# PCB_DYBoard_Collector_V1_Sh2.net
KiCad netlist of a schematic drawn in Altium Designer
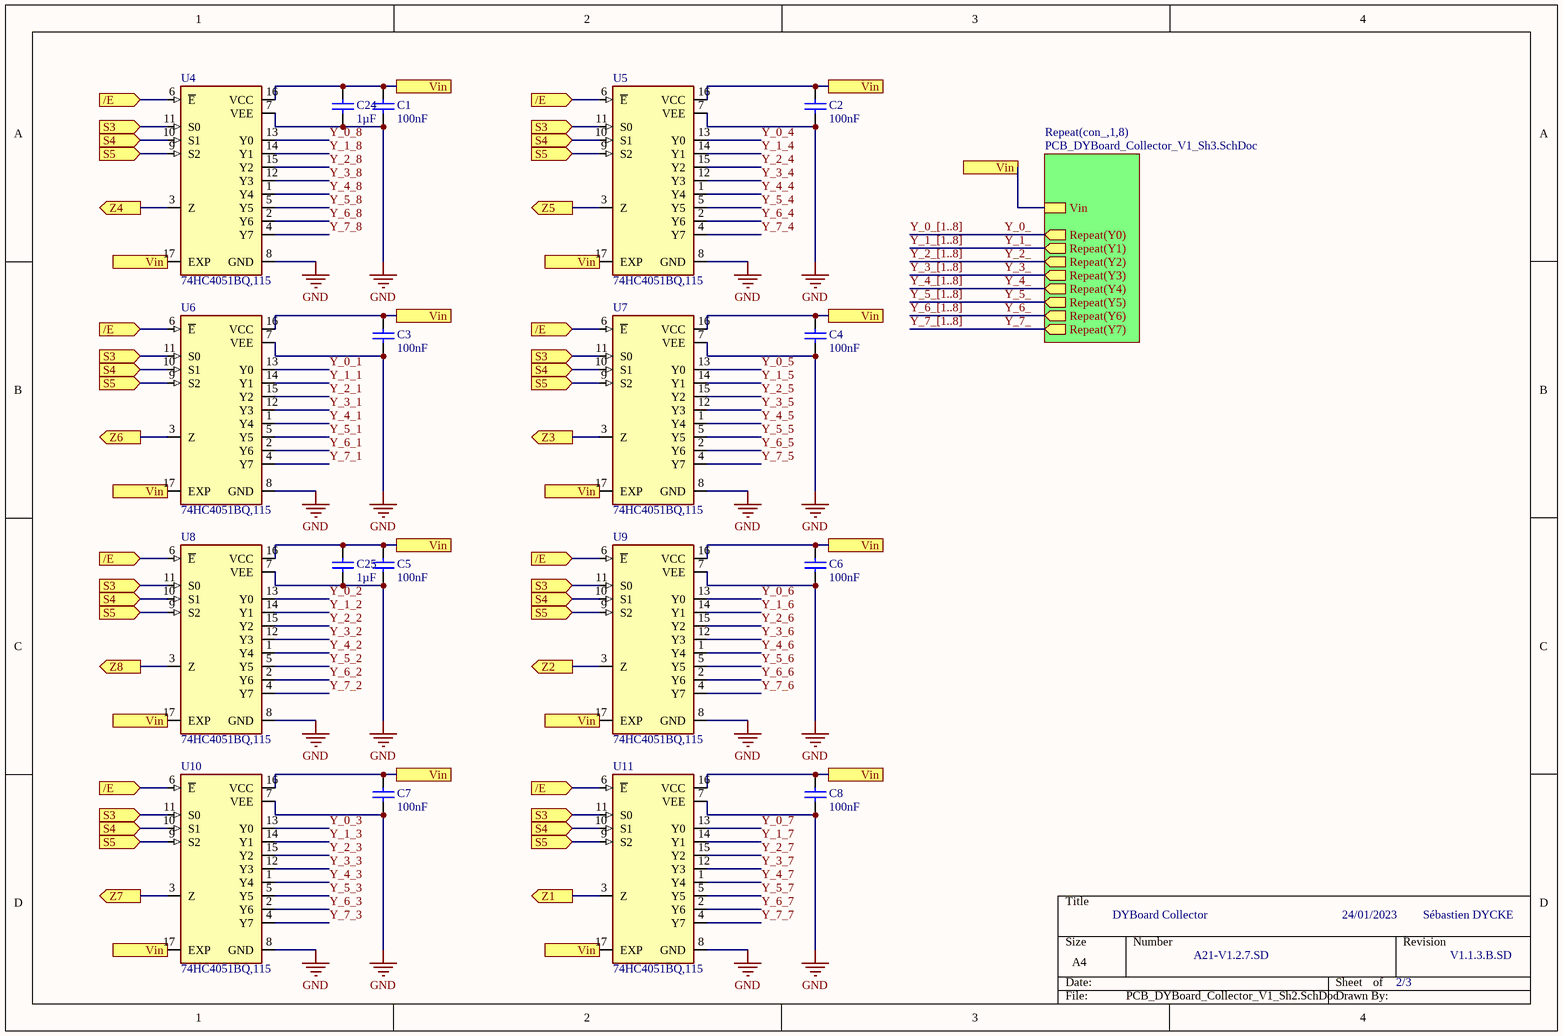
[diagram p0: PCB_DYBoard_Collector_V1_Sh2.SchDoc]

(export (version "E")
  (design (tool "Eeschema 10.0.6"))
  (components
    (comp (ref "C1")
      (value "100nF")
      (footprint "1608[0603]")
      (description "Capacitor (Semiconductor SIM Model)")
      (fields (field (name "Comment") "Cap Semi") (field (name "PUBLISHER") "Altium Limited"))
      (libsource (lib "Miscellaneous Devices") (part "Cap Semi"))
    )
    (comp (ref "C2")
      (value "100nF")
      (footprint "1608[0603]")
      (description "Capacitor (Semiconductor SIM Model)")
      (fields (field (name "Comment") "Cap Semi") (field (name "PUBLISHER") "Altium Limited"))
      (libsource (lib "Miscellaneous Devices") (part "Cap Semi"))
    )
    (comp (ref "C3")
      (value "100nF")
      (footprint "1608[0603]")
      (description "Capacitor (Semiconductor SIM Model)")
      (fields (field (name "Comment") "Cap Semi") (field (name "PUBLISHER") "Altium Limited"))
      (libsource (lib "Miscellaneous Devices") (part "Cap Semi"))
    )
    (comp (ref "C4")
      (value "100nF")
      (footprint "1608[0603]")
      (description "Capacitor (Semiconductor SIM Model)")
      (fields (field (name "Comment") "Cap Semi") (field (name "PUBLISHER") "Altium Limited"))
      (libsource (lib "Miscellaneous Devices") (part "Cap Semi"))
    )
    (comp (ref "C5")
      (value "100nF")
      (footprint "1608[0603]")
      (description "Capacitor (Semiconductor SIM Model)")
      (fields (field (name "Comment") "Cap Semi") (field (name "PUBLISHER") "Altium Limited"))
      (libsource (lib "Miscellaneous Devices") (part "Cap Semi"))
    )
    (comp (ref "C6")
      (value "100nF")
      (footprint "1608[0603]")
      (description "Capacitor (Semiconductor SIM Model)")
      (fields (field (name "Comment") "Cap Semi") (field (name "PUBLISHER") "Altium Limited"))
      (libsource (lib "Miscellaneous Devices") (part "Cap Semi"))
    )
    (comp (ref "C7")
      (value "100nF")
      (footprint "1608[0603]")
      (description "Capacitor (Semiconductor SIM Model)")
      (fields (field (name "Comment") "Cap Semi") (field (name "PUBLISHER") "Altium Limited"))
      (libsource (lib "Miscellaneous Devices") (part "Cap Semi"))
    )
    (comp (ref "C8")
      (value "100nF")
      (footprint "1608[0603]")
      (description "Capacitor (Semiconductor SIM Model)")
      (fields (field (name "Comment") "Cap Semi") (field (name "PUBLISHER") "Altium Limited"))
      (libsource (lib "Miscellaneous Devices") (part "Cap Semi"))
    )
    (comp (ref "C24")
      (value "1µF")
      (footprint "1608[0603]")
      (description "Capacitor (Semiconductor SIM Model)")
      (fields (field (name "Comment") "Cap Semi") (field (name "PUBLISHER") "Altium Limited"))
      (libsource (lib "Miscellaneous Devices") (part "Cap Semi"))
    )
    (comp (ref "C25")
      (value "1µF")
      (footprint "1608[0603]")
      (description "Capacitor (Semiconductor SIM Model)")
      (fields (field (name "Comment") "Cap Semi") (field (name "PUBLISHER") "Altium Limited"))
      (libsource (lib "Miscellaneous Devices") (part "Cap Semi"))
    )
    (comp (ref "U4")
      (value "74HC4051BQ,115")
      (footprint "QFN50P250X350X100-17N")
      (description "1 Circuit IC Switch 8:1 120Ohm 16-DHVQFN _2.5x3.5_")
      (fields (field (name "MF") "Nexperia USA"))
      (libsource (lib "74HC4051BQ_115") (part "74HC4051BQ,115"))
    )
    (comp (ref "U5")
      (value "74HC4051BQ,115")
      (footprint "QFN50P250X350X100-17N")
      (description "1 Circuit IC Switch 8:1 120Ohm 16-DHVQFN _2.5x3.5_")
      (fields (field (name "MF") "Nexperia USA"))
      (libsource (lib "74HC4051BQ_115") (part "74HC4051BQ,115"))
    )
    (comp (ref "U6")
      (value "74HC4051BQ,115")
      (footprint "QFN50P250X350X100-17N")
      (description "1 Circuit IC Switch 8:1 120Ohm 16-DHVQFN _2.5x3.5_")
      (fields (field (name "MF") "Nexperia USA"))
      (libsource (lib "74HC4051BQ_115") (part "74HC4051BQ,115"))
    )
    (comp (ref "U7")
      (value "74HC4051BQ,115")
      (footprint "QFN50P250X350X100-17N")
      (description "1 Circuit IC Switch 8:1 120Ohm 16-DHVQFN _2.5x3.5_")
      (fields (field (name "MF") "Nexperia USA"))
      (libsource (lib "74HC4051BQ_115") (part "74HC4051BQ,115"))
    )
    (comp (ref "U8")
      (value "74HC4051BQ,115")
      (footprint "QFN50P250X350X100-17N")
      (description "1 Circuit IC Switch 8:1 120Ohm 16-DHVQFN _2.5x3.5_")
      (fields (field (name "MF") "Nexperia USA"))
      (libsource (lib "74HC4051BQ_115") (part "74HC4051BQ,115"))
    )
    (comp (ref "U9")
      (value "74HC4051BQ,115")
      (footprint "QFN50P250X350X100-17N")
      (description "1 Circuit IC Switch 8:1 120Ohm 16-DHVQFN _2.5x3.5_")
      (fields (field (name "MF") "Nexperia USA"))
      (libsource (lib "74HC4051BQ_115") (part "74HC4051BQ,115"))
    )
    (comp (ref "U10")
      (value "74HC4051BQ,115")
      (footprint "QFN50P250X350X100-17N")
      (description "1 Circuit IC Switch 8:1 120Ohm 16-DHVQFN _2.5x3.5_")
      (fields (field (name "MF") "Nexperia USA"))
      (libsource (lib "74HC4051BQ_115") (part "74HC4051BQ,115"))
    )
    (comp (ref "U11")
      (value "74HC4051BQ,115")
      (footprint "QFN50P250X350X100-17N")
      (description "1 Circuit IC Switch 8:1 120Ohm 16-DHVQFN _2.5x3.5_")
      (fields (field (name "MF") "Nexperia USA"))
      (libsource (lib "74HC4051BQ_115") (part "74HC4051BQ,115"))
    )
  )
  (nets
    (net (code "1") (name "/S3") (class "Default")
      (node (ref "U10") (pin "11") (pinfunction "S0_11") (pintype "input"))
      (node (ref "U11") (pin "11") (pinfunction "S0_11") (pintype "input"))
      (node (ref "U4") (pin "11") (pinfunction "S0_11") (pintype "input"))
      (node (ref "U5") (pin "11") (pinfunction "S0_11") (pintype "input"))
      (node (ref "U6") (pin "11") (pinfunction "S0_11") (pintype "input"))
      (node (ref "U7") (pin "11") (pinfunction "S0_11") (pintype "input"))
      (node (ref "U8") (pin "11") (pinfunction "S0_11") (pintype "input"))
      (node (ref "U9") (pin "11") (pinfunction "S0_11") (pintype "input"))
    )
    (net (code "2") (name "/S4") (class "Default")
      (node (ref "U10") (pin "10") (pinfunction "S1_10") (pintype "input"))
      (node (ref "U11") (pin "10") (pinfunction "S1_10") (pintype "input"))
      (node (ref "U4") (pin "10") (pinfunction "S1_10") (pintype "input"))
      (node (ref "U5") (pin "10") (pinfunction "S1_10") (pintype "input"))
      (node (ref "U6") (pin "10") (pinfunction "S1_10") (pintype "input"))
      (node (ref "U7") (pin "10") (pinfunction "S1_10") (pintype "input"))
      (node (ref "U8") (pin "10") (pinfunction "S1_10") (pintype "input"))
      (node (ref "U9") (pin "10") (pinfunction "S1_10") (pintype "input"))
    )
    (net (code "3") (name "/S5") (class "Default")
      (node (ref "U10") (pin "9") (pinfunction "S2_9") (pintype "input"))
      (node (ref "U11") (pin "9") (pinfunction "S2_9") (pintype "input"))
      (node (ref "U4") (pin "9") (pinfunction "S2_9") (pintype "input"))
      (node (ref "U5") (pin "9") (pinfunction "S2_9") (pintype "input"))
      (node (ref "U6") (pin "9") (pinfunction "S2_9") (pintype "input"))
      (node (ref "U7") (pin "9") (pinfunction "S2_9") (pintype "input"))
      (node (ref "U8") (pin "9") (pinfunction "S2_9") (pintype "input"))
      (node (ref "U9") (pin "9") (pinfunction "S2_9") (pintype "input"))
    )
    (net (code "4") (name "/Vin") (class "Default")
      (node (ref "C1") (pin "2") (pinfunction "2_2") (pintype "passive"))
      (node (ref "C2") (pin "2") (pinfunction "2_2") (pintype "passive"))
      (node (ref "C24") (pin "2") (pinfunction "2_2") (pintype "passive"))
      (node (ref "C25") (pin "2") (pinfunction "2_2") (pintype "passive"))
      (node (ref "C3") (pin "2") (pinfunction "2_2") (pintype "passive"))
      (node (ref "C4") (pin "2") (pinfunction "2_2") (pintype "passive"))
      (node (ref "C5") (pin "2") (pinfunction "2_2") (pintype "passive"))
      (node (ref "C6") (pin "2") (pinfunction "2_2") (pintype "passive"))
      (node (ref "C7") (pin "2") (pinfunction "2_2") (pintype "passive"))
      (node (ref "C8") (pin "2") (pinfunction "2_2") (pintype "passive"))
      (node (ref "U10") (pin "16") (pinfunction "VCC_16") (pintype "power_in"))
      (node (ref "U10") (pin "17") (pinfunction "EXP_17") (pintype "power_in"))
      (node (ref "U11") (pin "16") (pinfunction "VCC_16") (pintype "power_in"))
      (node (ref "U11") (pin "17") (pinfunction "EXP_17") (pintype "power_in"))
      (node (ref "U4") (pin "16") (pinfunction "VCC_16") (pintype "power_in"))
      (node (ref "U4") (pin "17") (pinfunction "EXP_17") (pintype "power_in"))
      (node (ref "U5") (pin "16") (pinfunction "VCC_16") (pintype "power_in"))
      (node (ref "U5") (pin "17") (pinfunction "EXP_17") (pintype "power_in"))
      (node (ref "U6") (pin "16") (pinfunction "VCC_16") (pintype "power_in"))
      (node (ref "U6") (pin "17") (pinfunction "EXP_17") (pintype "power_in"))
      (node (ref "U7") (pin "16") (pinfunction "VCC_16") (pintype "power_in"))
      (node (ref "U7") (pin "17") (pinfunction "EXP_17") (pintype "power_in"))
      (node (ref "U8") (pin "16") (pinfunction "VCC_16") (pintype "power_in"))
      (node (ref "U8") (pin "17") (pinfunction "EXP_17") (pintype "power_in"))
      (node (ref "U9") (pin "16") (pinfunction "VCC_16") (pintype "power_in"))
      (node (ref "U9") (pin "17") (pinfunction "EXP_17") (pintype "power_in"))
    )
    (net (code "6") (name "/Y_0_1") (class "Default")
      (node (ref "U6") (pin "13") (pinfunction "Y0_13") (pintype "bidirectional"))
    )
    (net (code "7") (name "/Y_0_2") (class "Default")
      (node (ref "U8") (pin "13") (pinfunction "Y0_13") (pintype "bidirectional"))
    )
    (net (code "8") (name "/Y_0_3") (class "Default")
      (node (ref "U10") (pin "13") (pinfunction "Y0_13") (pintype "bidirectional"))
    )
    (net (code "9") (name "/Y_0_4") (class "Default")
      (node (ref "U5") (pin "13") (pinfunction "Y0_13") (pintype "bidirectional"))
    )
    (net (code "10") (name "/Y_0_5") (class "Default")
      (node (ref "U7") (pin "13") (pinfunction "Y0_13") (pintype "bidirectional"))
    )
    (net (code "11") (name "/Y_0_6") (class "Default")
      (node (ref "U9") (pin "13") (pinfunction "Y0_13") (pintype "bidirectional"))
    )
    (net (code "12") (name "/Y_0_7") (class "Default")
      (node (ref "U11") (pin "13") (pinfunction "Y0_13") (pintype "bidirectional"))
    )
    (net (code "13") (name "/Y_0_8") (class "Default")
      (node (ref "U4") (pin "13") (pinfunction "Y0_13") (pintype "bidirectional"))
    )
    (net (code "16") (name "/Y_1_1") (class "Default")
      (node (ref "U6") (pin "14") (pinfunction "Y1_14") (pintype "bidirectional"))
    )
    (net (code "17") (name "/Y_1_2") (class "Default")
      (node (ref "U8") (pin "14") (pinfunction "Y1_14") (pintype "bidirectional"))
    )
    (net (code "18") (name "/Y_1_3") (class "Default")
      (node (ref "U10") (pin "14") (pinfunction "Y1_14") (pintype "bidirectional"))
    )
    (net (code "19") (name "/Y_1_4") (class "Default")
      (node (ref "U5") (pin "14") (pinfunction "Y1_14") (pintype "bidirectional"))
    )
    (net (code "20") (name "/Y_1_5") (class "Default")
      (node (ref "U7") (pin "14") (pinfunction "Y1_14") (pintype "bidirectional"))
    )
    (net (code "21") (name "/Y_1_6") (class "Default")
      (node (ref "U9") (pin "14") (pinfunction "Y1_14") (pintype "bidirectional"))
    )
    (net (code "22") (name "/Y_1_7") (class "Default")
      (node (ref "U11") (pin "14") (pinfunction "Y1_14") (pintype "bidirectional"))
    )
    (net (code "23") (name "/Y_1_8") (class "Default")
      (node (ref "U4") (pin "14") (pinfunction "Y1_14") (pintype "bidirectional"))
    )
    (net (code "26") (name "/Y_2_1") (class "Default")
      (node (ref "U6") (pin "15") (pinfunction "Y2_15") (pintype "bidirectional"))
    )
    (net (code "27") (name "/Y_2_2") (class "Default")
      (node (ref "U8") (pin "15") (pinfunction "Y2_15") (pintype "bidirectional"))
    )
    (net (code "28") (name "/Y_2_3") (class "Default")
      (node (ref "U10") (pin "15") (pinfunction "Y2_15") (pintype "bidirectional"))
    )
    (net (code "29") (name "/Y_2_4") (class "Default")
      (node (ref "U5") (pin "15") (pinfunction "Y2_15") (pintype "bidirectional"))
    )
    (net (code "30") (name "/Y_2_5") (class "Default")
      (node (ref "U7") (pin "15") (pinfunction "Y2_15") (pintype "bidirectional"))
    )
    (net (code "31") (name "/Y_2_6") (class "Default")
      (node (ref "U9") (pin "15") (pinfunction "Y2_15") (pintype "bidirectional"))
    )
    (net (code "32") (name "/Y_2_7") (class "Default")
      (node (ref "U11") (pin "15") (pinfunction "Y2_15") (pintype "bidirectional"))
    )
    (net (code "33") (name "/Y_2_8") (class "Default")
      (node (ref "U4") (pin "15") (pinfunction "Y2_15") (pintype "bidirectional"))
    )
    (net (code "36") (name "/Y_3_1") (class "Default")
      (node (ref "U6") (pin "12") (pinfunction "Y3_12") (pintype "bidirectional"))
    )
    (net (code "37") (name "/Y_3_2") (class "Default")
      (node (ref "U8") (pin "12") (pinfunction "Y3_12") (pintype "bidirectional"))
    )
    (net (code "38") (name "/Y_3_3") (class "Default")
      (node (ref "U10") (pin "12") (pinfunction "Y3_12") (pintype "bidirectional"))
    )
    (net (code "39") (name "/Y_3_4") (class "Default")
      (node (ref "U5") (pin "12") (pinfunction "Y3_12") (pintype "bidirectional"))
    )
    (net (code "40") (name "/Y_3_5") (class "Default")
      (node (ref "U7") (pin "12") (pinfunction "Y3_12") (pintype "bidirectional"))
    )
    (net (code "41") (name "/Y_3_6") (class "Default")
      (node (ref "U9") (pin "12") (pinfunction "Y3_12") (pintype "bidirectional"))
    )
    (net (code "42") (name "/Y_3_7") (class "Default")
      (node (ref "U11") (pin "12") (pinfunction "Y3_12") (pintype "bidirectional"))
    )
    (net (code "43") (name "/Y_3_8") (class "Default")
      (node (ref "U4") (pin "12") (pinfunction "Y3_12") (pintype "bidirectional"))
    )
    (net (code "46") (name "/Y_4_1") (class "Default")
      (node (ref "U6") (pin "1") (pinfunction "Y4_1") (pintype "bidirectional"))
    )
    (net (code "47") (name "/Y_4_2") (class "Default")
      (node (ref "U8") (pin "1") (pinfunction "Y4_1") (pintype "bidirectional"))
    )
    (net (code "48") (name "/Y_4_3") (class "Default")
      (node (ref "U10") (pin "1") (pinfunction "Y4_1") (pintype "bidirectional"))
    )
    (net (code "49") (name "/Y_4_4") (class "Default")
      (node (ref "U5") (pin "1") (pinfunction "Y4_1") (pintype "bidirectional"))
    )
    (net (code "50") (name "/Y_4_5") (class "Default")
      (node (ref "U7") (pin "1") (pinfunction "Y4_1") (pintype "bidirectional"))
    )
    (net (code "51") (name "/Y_4_6") (class "Default")
      (node (ref "U9") (pin "1") (pinfunction "Y4_1") (pintype "bidirectional"))
    )
    (net (code "52") (name "/Y_4_7") (class "Default")
      (node (ref "U11") (pin "1") (pinfunction "Y4_1") (pintype "bidirectional"))
    )
    (net (code "53") (name "/Y_4_8") (class "Default")
      (node (ref "U4") (pin "1") (pinfunction "Y4_1") (pintype "bidirectional"))
    )
    (net (code "56") (name "/Y_5_1") (class "Default")
      (node (ref "U6") (pin "5") (pinfunction "Y5_5") (pintype "bidirectional"))
    )
    (net (code "57") (name "/Y_5_2") (class "Default")
      (node (ref "U8") (pin "5") (pinfunction "Y5_5") (pintype "bidirectional"))
    )
    (net (code "58") (name "/Y_5_3") (class "Default")
      (node (ref "U10") (pin "5") (pinfunction "Y5_5") (pintype "bidirectional"))
    )
    (net (code "59") (name "/Y_5_4") (class "Default")
      (node (ref "U5") (pin "5") (pinfunction "Y5_5") (pintype "bidirectional"))
    )
    (net (code "60") (name "/Y_5_5") (class "Default")
      (node (ref "U7") (pin "5") (pinfunction "Y5_5") (pintype "bidirectional"))
    )
    (net (code "61") (name "/Y_5_6") (class "Default")
      (node (ref "U9") (pin "5") (pinfunction "Y5_5") (pintype "bidirectional"))
    )
    (net (code "62") (name "/Y_5_7") (class "Default")
      (node (ref "U11") (pin "5") (pinfunction "Y5_5") (pintype "bidirectional"))
    )
    (net (code "63") (name "/Y_5_8") (class "Default")
      (node (ref "U4") (pin "5") (pinfunction "Y5_5") (pintype "bidirectional"))
    )
    (net (code "66") (name "/Y_6_1") (class "Default")
      (node (ref "U6") (pin "2") (pinfunction "Y6_2") (pintype "bidirectional"))
    )
    (net (code "67") (name "/Y_6_2") (class "Default")
      (node (ref "U8") (pin "2") (pinfunction "Y6_2") (pintype "bidirectional"))
    )
    (net (code "68") (name "/Y_6_3") (class "Default")
      (node (ref "U10") (pin "2") (pinfunction "Y6_2") (pintype "bidirectional"))
    )
    (net (code "69") (name "/Y_6_4") (class "Default")
      (node (ref "U5") (pin "2") (pinfunction "Y6_2") (pintype "bidirectional"))
    )
    (net (code "70") (name "/Y_6_5") (class "Default")
      (node (ref "U7") (pin "2") (pinfunction "Y6_2") (pintype "bidirectional"))
    )
    (net (code "71") (name "/Y_6_6") (class "Default")
      (node (ref "U9") (pin "2") (pinfunction "Y6_2") (pintype "bidirectional"))
    )
    (net (code "72") (name "/Y_6_7") (class "Default")
      (node (ref "U11") (pin "2") (pinfunction "Y6_2") (pintype "bidirectional"))
    )
    (net (code "73") (name "/Y_6_8") (class "Default")
      (node (ref "U4") (pin "2") (pinfunction "Y6_2") (pintype "bidirectional"))
    )
    (net (code "76") (name "/Y_7_1") (class "Default")
      (node (ref "U6") (pin "4") (pinfunction "Y7_4") (pintype "bidirectional"))
    )
    (net (code "77") (name "/Y_7_2") (class "Default")
      (node (ref "U8") (pin "4") (pinfunction "Y7_4") (pintype "bidirectional"))
    )
    (net (code "78") (name "/Y_7_3") (class "Default")
      (node (ref "U10") (pin "4") (pinfunction "Y7_4") (pintype "bidirectional"))
    )
    (net (code "79") (name "/Y_7_4") (class "Default")
      (node (ref "U5") (pin "4") (pinfunction "Y7_4") (pintype "bidirectional"))
    )
    (net (code "80") (name "/Y_7_5") (class "Default")
      (node (ref "U7") (pin "4") (pinfunction "Y7_4") (pintype "bidirectional"))
    )
    (net (code "81") (name "/Y_7_6") (class "Default")
      (node (ref "U9") (pin "4") (pinfunction "Y7_4") (pintype "bidirectional"))
    )
    (net (code "82") (name "/Y_7_7") (class "Default")
      (node (ref "U11") (pin "4") (pinfunction "Y7_4") (pintype "bidirectional"))
    )
    (net (code "83") (name "/Y_7_8") (class "Default")
      (node (ref "U4") (pin "4") (pinfunction "Y7_4") (pintype "bidirectional"))
    )
    (net (code "85") (name "/Z1") (class "Default")
      (node (ref "U11") (pin "3") (pinfunction "Z_3") (pintype "bidirectional"))
    )
    (net (code "86") (name "/Z2") (class "Default")
      (node (ref "U9") (pin "3") (pinfunction "Z_3") (pintype "bidirectional"))
    )
    (net (code "87") (name "/Z3") (class "Default")
      (node (ref "U7") (pin "3") (pinfunction "Z_3") (pintype "bidirectional"))
    )
    (net (code "88") (name "/Z4") (class "Default")
      (node (ref "U4") (pin "3") (pinfunction "Z_3") (pintype "bidirectional"))
    )
    (net (code "89") (name "/Z5") (class "Default")
      (node (ref "U5") (pin "3") (pinfunction "Z_3") (pintype "bidirectional"))
    )
    (net (code "90") (name "/Z6") (class "Default")
      (node (ref "U6") (pin "3") (pinfunction "Z_3") (pintype "bidirectional"))
    )
    (net (code "91") (name "/Z7") (class "Default")
      (node (ref "U10") (pin "3") (pinfunction "Z_3") (pintype "bidirectional"))
    )
    (net (code "92") (name "/Z8") (class "Default")
      (node (ref "U8") (pin "3") (pinfunction "Z_3") (pintype "bidirectional"))
    )
    (net (code "93") (name "/{slash}E") (class "Default")
      (node (ref "U10") (pin "6") (pinfunction "~{E}_6") (pintype "input"))
      (node (ref "U11") (pin "6") (pinfunction "~{E}_6") (pintype "input"))
      (node (ref "U4") (pin "6") (pinfunction "~{E}_6") (pintype "input"))
      (node (ref "U5") (pin "6") (pinfunction "~{E}_6") (pintype "input"))
      (node (ref "U6") (pin "6") (pinfunction "~{E}_6") (pintype "input"))
      (node (ref "U7") (pin "6") (pinfunction "~{E}_6") (pintype "input"))
      (node (ref "U8") (pin "6") (pinfunction "~{E}_6") (pintype "input"))
      (node (ref "U9") (pin "6") (pinfunction "~{E}_6") (pintype "input"))
    )
    (net (code "94") (name "GND") (class "Default")
      (node (ref "C1") (pin "1") (pinfunction "1_1") (pintype "passive"))
      (node (ref "C2") (pin "1") (pinfunction "1_1") (pintype "passive"))
      (node (ref "C24") (pin "1") (pinfunction "1_1") (pintype "passive"))
      (node (ref "C25") (pin "1") (pinfunction "1_1") (pintype "passive"))
      (node (ref "C3") (pin "1") (pinfunction "1_1") (pintype "passive"))
      (node (ref "C4") (pin "1") (pinfunction "1_1") (pintype "passive"))
      (node (ref "C5") (pin "1") (pinfunction "1_1") (pintype "passive"))
      (node (ref "C6") (pin "1") (pinfunction "1_1") (pintype "passive"))
      (node (ref "C7") (pin "1") (pinfunction "1_1") (pintype "passive"))
      (node (ref "C8") (pin "1") (pinfunction "1_1") (pintype "passive"))
      (node (ref "U10") (pin "7") (pinfunction "VEE_7") (pintype "power_in"))
      (node (ref "U10") (pin "8") (pinfunction "GND_8") (pintype "power_in"))
      (node (ref "U11") (pin "7") (pinfunction "VEE_7") (pintype "power_in"))
      (node (ref "U11") (pin "8") (pinfunction "GND_8") (pintype "power_in"))
      (node (ref "U4") (pin "7") (pinfunction "VEE_7") (pintype "power_in"))
      (node (ref "U4") (pin "8") (pinfunction "GND_8") (pintype "power_in"))
      (node (ref "U5") (pin "7") (pinfunction "VEE_7") (pintype "power_in"))
      (node (ref "U5") (pin "8") (pinfunction "GND_8") (pintype "power_in"))
      (node (ref "U6") (pin "7") (pinfunction "VEE_7") (pintype "power_in"))
      (node (ref "U6") (pin "8") (pinfunction "GND_8") (pintype "power_in"))
      (node (ref "U7") (pin "7") (pinfunction "VEE_7") (pintype "power_in"))
      (node (ref "U7") (pin "8") (pinfunction "GND_8") (pintype "power_in"))
      (node (ref "U8") (pin "7") (pinfunction "VEE_7") (pintype "power_in"))
      (node (ref "U8") (pin "8") (pinfunction "GND_8") (pintype "power_in"))
      (node (ref "U9") (pin "7") (pinfunction "VEE_7") (pintype "power_in"))
      (node (ref "U9") (pin "8") (pinfunction "GND_8") (pintype "power_in"))
    )
  )
)
